# MainBoard_MCU_PWR.net
KiCad netlist of a schematic drawn in Altium Designer
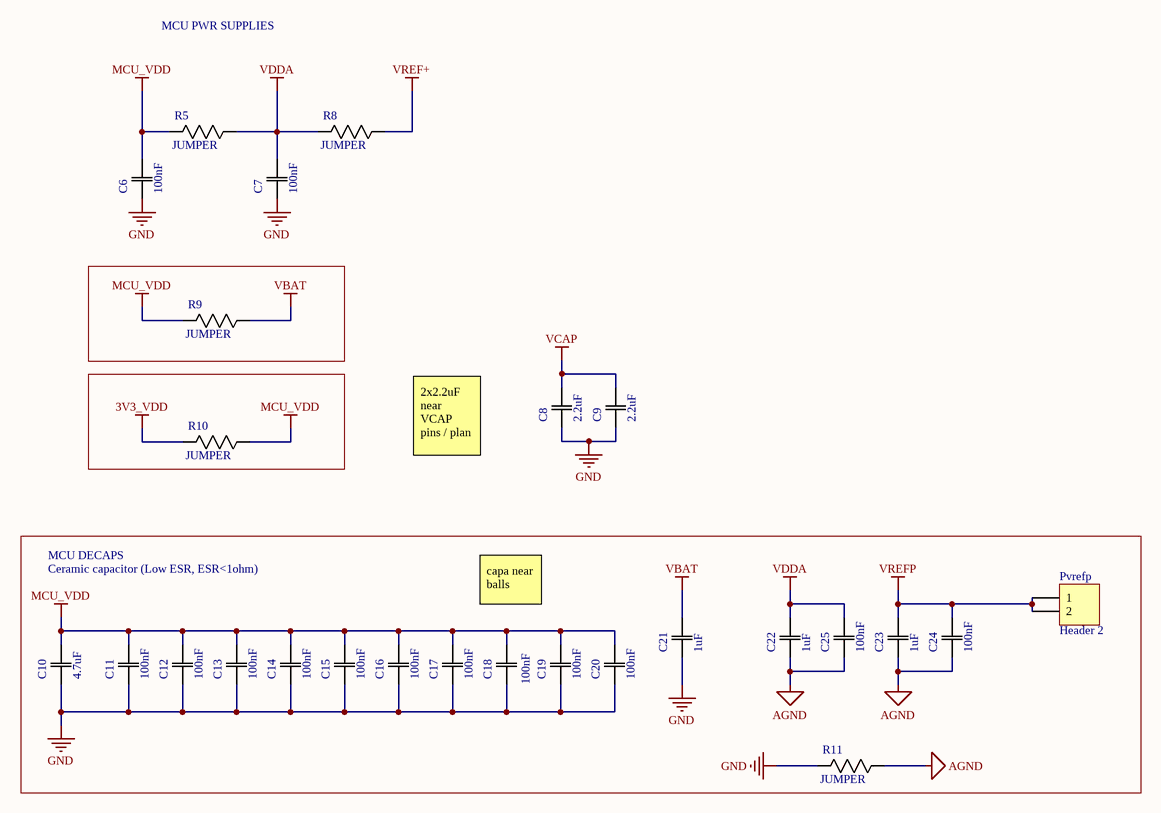
[diagram p0: MainBoard_MCU_PWR.SchDoc]

(export (version "E")
  (design (tool "Eeschema 10.0.6"))
  (components
    (comp (ref "C6")
      (value "100nF")
      (footprint "0805")
      (description "CAP CER 0.1UF 50V X7R 0805")
      (fields (field (name "MP") "CC0805KRX7R9BB104") (field (name "MF") "Yageo"))
      (libsource (lib "AltiumLibraries") (part "CAP 100nF 0805"))
    )
    (comp (ref "C7")
      (value "100nF")
      (footprint "0805")
      (description "CAP CER 0.1UF 50V X7R 0805")
      (fields (field (name "MP") "CC0805KRX7R9BB104") (field (name "MF") "Yageo"))
      (libsource (lib "AltiumLibraries") (part "CAP 100nF 0805"))
    )
    (comp (ref "C8")
      (value "2.2uF")
      (footprint "0805")
      (description "CAP CER 1UF 50V X7R 0805")
      (fields (field (name "MP") "C0805C225K4RACTU") (field (name "MF") "KEMET"))
      (libsource (lib "AltiumLibraries") (part "CAP 2.2uF 0805"))
    )
    (comp (ref "C9")
      (value "2.2uF")
      (footprint "0805")
      (description "CAP CER 1UF 50V X7R 0805")
      (fields (field (name "MP") "C0805C225K4RACTU") (field (name "MF") "KEMET"))
      (libsource (lib "AltiumLibraries") (part "CAP 2.2uF 0805"))
    )
    (comp (ref "C10")
      (value "4.7uF")
      (footprint "0805")
      (description "CAP CER 4.7UF 25V X5R 0805")
      (fields (field (name "MP") "CL21B475KOFNNNE") (field (name "MF") "Samsung Electro-Mechanics"))
      (libsource (lib "AltiumLibraries") (part "CAP 4.7uF 0805"))
    )
    (comp (ref "C11")
      (value "100nF")
      (footprint "0805")
      (description "CAP CER 0.1UF 50V X7R 0805")
      (fields (field (name "MP") "CC0805KRX7R9BB104") (field (name "MF") "Yageo"))
      (libsource (lib "AltiumLibraries") (part "CAP 100nF 0805"))
    )
    (comp (ref "C12")
      (value "100nF")
      (footprint "0805")
      (description "CAP CER 0.1UF 50V X7R 0805")
      (fields (field (name "MP") "CC0805KRX7R9BB104") (field (name "MF") "Yageo"))
      (libsource (lib "AltiumLibraries") (part "CAP 100nF 0805"))
    )
    (comp (ref "C13")
      (value "100nF")
      (footprint "0805")
      (description "CAP CER 0.1UF 50V X7R 0805")
      (fields (field (name "MP") "CC0805KRX7R9BB104") (field (name "MF") "Yageo"))
      (libsource (lib "AltiumLibraries") (part "CAP 100nF 0805"))
    )
    (comp (ref "C14")
      (value "100nF")
      (footprint "0805")
      (description "CAP CER 0.1UF 50V X7R 0805")
      (fields (field (name "MP") "CC0805KRX7R9BB104") (field (name "MF") "Yageo"))
      (libsource (lib "AltiumLibraries") (part "CAP 100nF 0805"))
    )
    (comp (ref "C15")
      (value "100nF")
      (footprint "0805")
      (description "CAP CER 0.1UF 50V X7R 0805")
      (fields (field (name "MP") "CC0805KRX7R9BB104") (field (name "MF") "Yageo"))
      (libsource (lib "AltiumLibraries") (part "CAP 100nF 0805"))
    )
    (comp (ref "C16")
      (value "100nF")
      (footprint "0805")
      (description "CAP CER 0.1UF 50V X7R 0805")
      (fields (field (name "MP") "CC0805KRX7R9BB104") (field (name "MF") "Yageo"))
      (libsource (lib "AltiumLibraries") (part "CAP 100nF 0805"))
    )
    (comp (ref "C17")
      (value "100nF")
      (footprint "0805")
      (description "CAP CER 0.1UF 50V X7R 0805")
      (fields (field (name "MP") "CC0805KRX7R9BB104") (field (name "MF") "Yageo"))
      (libsource (lib "AltiumLibraries") (part "CAP 100nF 0805"))
    )
    (comp (ref "C18")
      (value "100nF")
      (footprint "0805")
      (description "CAP CER 0.1UF 50V X7R 0805")
      (fields (field (name "MP") "CC0805KRX7R9BB104") (field (name "MF") "Yageo"))
      (libsource (lib "AltiumLibraries") (part "CAP 100nF 0805"))
    )
    (comp (ref "C19")
      (value "100nF")
      (footprint "0805")
      (description "CAP CER 0.1UF 50V X7R 0805")
      (fields (field (name "MP") "CC0805KRX7R9BB104") (field (name "MF") "Yageo"))
      (libsource (lib "AltiumLibraries") (part "CAP 100nF 0805"))
    )
    (comp (ref "C20")
      (value "100nF")
      (footprint "0805")
      (description "CAP CER 0.1UF 50V X7R 0805")
      (fields (field (name "MP") "CC0805KRX7R9BB104") (field (name "MF") "Yageo"))
      (libsource (lib "AltiumLibraries") (part "CAP 100nF 0805"))
    )
    (comp (ref "C21")
      (value "1uF")
      (footprint "0805")
      (description "CAP CER 1UF 50V X7R 0805")
      (fields (field (name "MP") "CL21B105KBFNNNE") (field (name "MF") "Samsung Electro-Mechanics"))
      (libsource (lib "AltiumLibraries") (part "CAP 1uF 0805"))
    )
    (comp (ref "C22")
      (value "1uF")
      (footprint "0805")
      (description "CAP CER 1UF 50V X7R 0805")
      (fields (field (name "MP") "CL21B105KBFNNNE") (field (name "MF") "Samsung Electro-Mechanics"))
      (libsource (lib "AltiumLibraries") (part "CAP 1uF 0805"))
    )
    (comp (ref "C23")
      (value "1uF")
      (footprint "0805")
      (description "CAP CER 1UF 50V X7R 0805")
      (fields (field (name "MP") "CL21B105KBFNNNE") (field (name "MF") "Samsung Electro-Mechanics"))
      (libsource (lib "AltiumLibraries") (part "CAP 1uF 0805"))
    )
    (comp (ref "C24")
      (value "100nF")
      (footprint "0805")
      (description "CAP CER 0.1UF 50V X7R 0805")
      (fields (field (name "MP") "CC0805KRX7R9BB104") (field (name "MF") "Yageo"))
      (libsource (lib "AltiumLibraries") (part "CAP 100nF 0805"))
    )
    (comp (ref "C25")
      (value "100nF")
      (footprint "0805")
      (description "CAP CER 0.1UF 50V X7R 0805")
      (fields (field (name "MP") "CC0805KRX7R9BB104") (field (name "MF") "Yageo"))
      (libsource (lib "AltiumLibraries") (part "CAP 100nF 0805"))
    )
    (comp (ref "Pvrefp")
      (value "Header 2")
      (footprint "HDR1X2")
      (description "Header, 2-Pin")
      (fields (field (name "PUBLISHER") "Altium Limited"))
      (libsource (lib "Miscellaneous Connectors") (part "Header 2"))
    )
    (comp (ref "R5")
      (value "JUMPER")
      (footprint "0805")
      (description "RES SMD 0 OHM JUMPER 1/8W 0805")
      (fields (field (name "MP") "RC0805JR-070RL") (field (name "MF") "Yageo"))
      (libsource (lib "AltiumLibraries") (part "RES 0 0805"))
    )
    (comp (ref "R8")
      (value "JUMPER")
      (footprint "0805")
      (description "RES SMD 0 OHM JUMPER 1/8W 0805")
      (fields (field (name "MP") "RC0805JR-070RL") (field (name "MF") "Yageo"))
      (libsource (lib "AltiumLibraries") (part "RES 0 0805"))
    )
    (comp (ref "R9")
      (value "JUMPER")
      (footprint "0805")
      (description "RES SMD 0 OHM JUMPER 1/8W 0805")
      (fields (field (name "MP") "RC0805JR-070RL") (field (name "MF") "Yageo"))
      (libsource (lib "AltiumLibraries") (part "RES 0 0805"))
    )
    (comp (ref "R10")
      (value "JUMPER")
      (footprint "0805")
      (description "RES SMD 0 OHM JUMPER 1/8W 0805")
      (fields (field (name "MP") "RC0805JR-070RL") (field (name "MF") "Yageo"))
      (libsource (lib "AltiumLibraries") (part "RES 0 0805"))
    )
    (comp (ref "R11")
      (value "JUMPER")
      (footprint "0805")
      (description "RES SMD 0 OHM JUMPER 1/8W 0805")
      (fields (field (name "MP") "RC0805JR-070RL") (field (name "MF") "Yageo"))
      (libsource (lib "AltiumLibraries") (part "RES 0 0805"))
    )
  )
  (nets
    (net (code "1") (name "3V3_VDD") (class "Default")
      (node (ref "R10") (pin "2") (pinfunction "R2_2") (pintype "passive"))
    )
    (net (code "2") (name "AGND") (class "Default")
      (node (ref "C22") (pin "1") (pinfunction "C1_1") (pintype "passive"))
      (node (ref "C23") (pin "1") (pinfunction "C1_1") (pintype "passive"))
      (node (ref "C24") (pin "1") (pinfunction "C1_1") (pintype "passive"))
      (node (ref "C25") (pin "1") (pinfunction "C1_1") (pintype "passive"))
      (node (ref "R11") (pin "1") (pinfunction "R1_1") (pintype "passive"))
    )
    (net (code "3") (name "GND") (class "Default")
      (node (ref "C10") (pin "1") (pinfunction "C1_1") (pintype "passive"))
      (node (ref "C11") (pin "1") (pinfunction "C1_1") (pintype "passive"))
      (node (ref "C12") (pin "1") (pinfunction "C1_1") (pintype "passive"))
      (node (ref "C13") (pin "1") (pinfunction "C1_1") (pintype "passive"))
      (node (ref "C14") (pin "1") (pinfunction "C1_1") (pintype "passive"))
      (node (ref "C15") (pin "1") (pinfunction "C1_1") (pintype "passive"))
      (node (ref "C16") (pin "1") (pinfunction "C1_1") (pintype "passive"))
      (node (ref "C17") (pin "1") (pinfunction "C1_1") (pintype "passive"))
      (node (ref "C18") (pin "1") (pinfunction "C1_1") (pintype "passive"))
      (node (ref "C19") (pin "1") (pinfunction "C1_1") (pintype "passive"))
      (node (ref "C20") (pin "1") (pinfunction "C1_1") (pintype "passive"))
      (node (ref "C21") (pin "1") (pinfunction "C1_1") (pintype "passive"))
      (node (ref "C6") (pin "1") (pinfunction "C1_1") (pintype "passive"))
      (node (ref "C7") (pin "1") (pinfunction "C1_1") (pintype "passive"))
      (node (ref "C8") (pin "1") (pinfunction "C1_1") (pintype "passive"))
      (node (ref "C9") (pin "1") (pinfunction "C1_1") (pintype "passive"))
      (node (ref "R11") (pin "2") (pinfunction "R2_2") (pintype "passive"))
    )
    (net (code "4") (name "MCU_VDD") (class "Default")
      (node (ref "C10") (pin "2") (pinfunction "C2_2") (pintype "passive"))
      (node (ref "C11") (pin "2") (pinfunction "C2_2") (pintype "passive"))
      (node (ref "C12") (pin "2") (pinfunction "C2_2") (pintype "passive"))
      (node (ref "C13") (pin "2") (pinfunction "C2_2") (pintype "passive"))
      (node (ref "C14") (pin "2") (pinfunction "C2_2") (pintype "passive"))
      (node (ref "C15") (pin "2") (pinfunction "C2_2") (pintype "passive"))
      (node (ref "C16") (pin "2") (pinfunction "C2_2") (pintype "passive"))
      (node (ref "C17") (pin "2") (pinfunction "C2_2") (pintype "passive"))
      (node (ref "C18") (pin "2") (pinfunction "C2_2") (pintype "passive"))
      (node (ref "C19") (pin "2") (pinfunction "C2_2") (pintype "passive"))
      (node (ref "C20") (pin "2") (pinfunction "C2_2") (pintype "passive"))
      (node (ref "C6") (pin "2") (pinfunction "C2_2") (pintype "passive"))
      (node (ref "R10") (pin "1") (pinfunction "R1_1") (pintype "passive"))
      (node (ref "R5") (pin "2") (pinfunction "R2_2") (pintype "passive"))
      (node (ref "R9") (pin "2") (pinfunction "R2_2") (pintype "passive"))
    )
    (net (code "5") (name "VBAT") (class "Default")
      (node (ref "C21") (pin "2") (pinfunction "C2_2") (pintype "passive"))
      (node (ref "R9") (pin "1") (pinfunction "R1_1") (pintype "passive"))
    )
    (net (code "6") (name "VCAP") (class "Default")
      (node (ref "C8") (pin "2") (pinfunction "C2_2") (pintype "passive"))
      (node (ref "C9") (pin "2") (pinfunction "C2_2") (pintype "passive"))
    )
    (net (code "7") (name "VDDA") (class "Default")
      (node (ref "C22") (pin "2") (pinfunction "C2_2") (pintype "passive"))
      (node (ref "C25") (pin "2") (pinfunction "C2_2") (pintype "passive"))
      (node (ref "C7") (pin "2") (pinfunction "C2_2") (pintype "passive"))
      (node (ref "R5") (pin "1") (pinfunction "R1_1") (pintype "passive"))
      (node (ref "R8") (pin "2") (pinfunction "R2_2") (pintype "passive"))
    )
    (net (code "8") (name "VREF+") (class "Default")
      (node (ref "R8") (pin "1") (pinfunction "R1_1") (pintype "passive"))
    )
    (net (code "9") (name "VREFP") (class "Default")
      (node (ref "C23") (pin "2") (pinfunction "C2_2") (pintype "passive"))
      (node (ref "C24") (pin "2") (pinfunction "C2_2") (pintype "passive"))
      (node (ref "Pvrefp") (pin "1") (pinfunction "1_1") (pintype "passive"))
      (node (ref "Pvrefp") (pin "2") (pinfunction "2_2") (pintype "passive"))
    )
  )
)
